# conn_ant_sch.net
KiCad netlist of a schematic drawn in Altium Designer
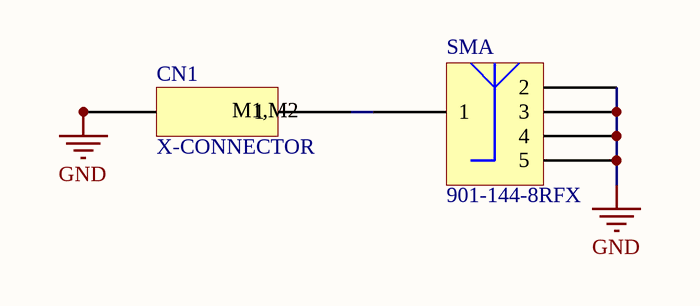
[diagram p0: conn_ant_sch.SchDoc]

(export (version "E")
  (design (tool "Eeschema 10.0.6"))
  (components
    (comp (ref "CN1")
      (value "X-CONNECTOR")
      (footprint "X-CONNECTOR-PCB")
      (description "CONECTOR PARA MÓDULOS X MICROWAVE")
      (libsource (lib "(LR)²") (part "X-CONNECTOR"))
    )
    (comp (ref "SMA")
      (value "901-144-8RFX")
      (footprint "901-144-8RFX-Footprint-1")
      (description "CONN SMA JACK STR 50 OHM PCB")
      (libsource (lib "IMBEL") (part "901-144-8RFX"))
    )
  )
  (nets
    (net (code "1") (name "GND") (class "Default")
      (node (ref "CN1") (pin "M1") (pinfunction "M1_M1") (pintype "passive"))
      (node (ref "CN1") (pin "M2") (pinfunction "M2_M2") (pintype "passive"))
      (node (ref "SMA") (pin "2") (pinfunction "2_2") (pintype "passive"))
      (node (ref "SMA") (pin "3") (pinfunction "3_3") (pintype "passive"))
      (node (ref "SMA") (pin "4") (pinfunction "4_4") (pintype "passive"))
      (node (ref "SMA") (pin "5") (pinfunction "5_5") (pintype "passive"))
    )
    (net (code "2") (name "Net-(CN1-Pad1)") (class "Default")
      (node (ref "CN1") (pin "1") (pinfunction "1_1") (pintype "passive"))
      (node (ref "SMA") (pin "1") (pinfunction "1_1") (pintype "passive"))
    )
  )
)
